# Bridge.net
KiCad netlist of a schematic drawn in EAGLE
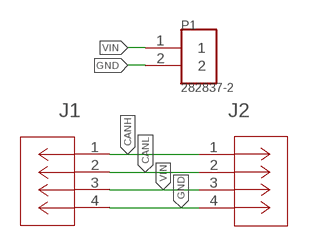
[diagram p0: schematic, sheet 1]

(export (version "E")
  (design (tool "Eeschema 10.0.6"))
  (components
    (comp (ref "J1")
      (value "22027043CONN4X1_22027043_MOL")
      (footprint "eagle-import:CONN4X1_22027043_MOL")
      (fields
        (field (name "MANUFACTURER_PART_NUMBER") "22027043")
        (field (name "COPYRIGHT") "Copyright (C) 2025 Ultra Librarian. All rights reserved.")
      )
      (libsource (lib "eagle-import") (part "22027043CONN4X1_22027043_MOL"))
    )
    (comp (ref "J2")
      (value "22027043CONN4X1_22027043_MOL")
      (footprint "eagle-import:CONN4X1_22027043_MOL")
      (fields
        (field (name "MANUFACTURER_PART_NUMBER") "22027043")
        (field (name "COPYRIGHT") "Copyright (C) 2025 Ultra Librarian. All rights reserved.")
      )
      (libsource (lib "eagle-import") (part "22027043CONN4X1_22027043_MOL"))
    )
    (comp (ref "P1")
      (value "282837-2")
      (footprint "eagle-import:TE_282837-2")
      (fields (field (name "MF") "TE Connectivity"))
      (libsource (lib "eagle-import") (part "282837-2"))
    )
  )
  (nets
    (net (code "1") (name "CANH") (class "Default")
      (node (ref "J1") (pin "1") (pinfunction "1_1") (pintype "passive"))
      (node (ref "J2") (pin "1") (pinfunction "1_1") (pintype "passive"))
    )
    (net (code "2") (name "CANL") (class "Default")
      (node (ref "J1") (pin "2") (pinfunction "2_2") (pintype "passive"))
      (node (ref "J2") (pin "2") (pinfunction "2_2") (pintype "passive"))
    )
    (net (code "3") (name "GND") (class "Default")
      (node (ref "J1") (pin "4") (pinfunction "4_4") (pintype "passive"))
      (node (ref "J2") (pin "4") (pinfunction "4_4") (pintype "passive"))
      (node (ref "P1") (pin "2") (pinfunction "2_2") (pintype "passive"))
    )
    (net (code "4") (name "VIN") (class "Default")
      (node (ref "J1") (pin "3") (pinfunction "3_3") (pintype "passive"))
      (node (ref "J2") (pin "3") (pinfunction "3_3") (pintype "passive"))
      (node (ref "P1") (pin "1") (pinfunction "1_1") (pintype "passive"))
    )
  )
)
